# TOP.net
KiCad netlist of a schematic drawn in Altium Designer
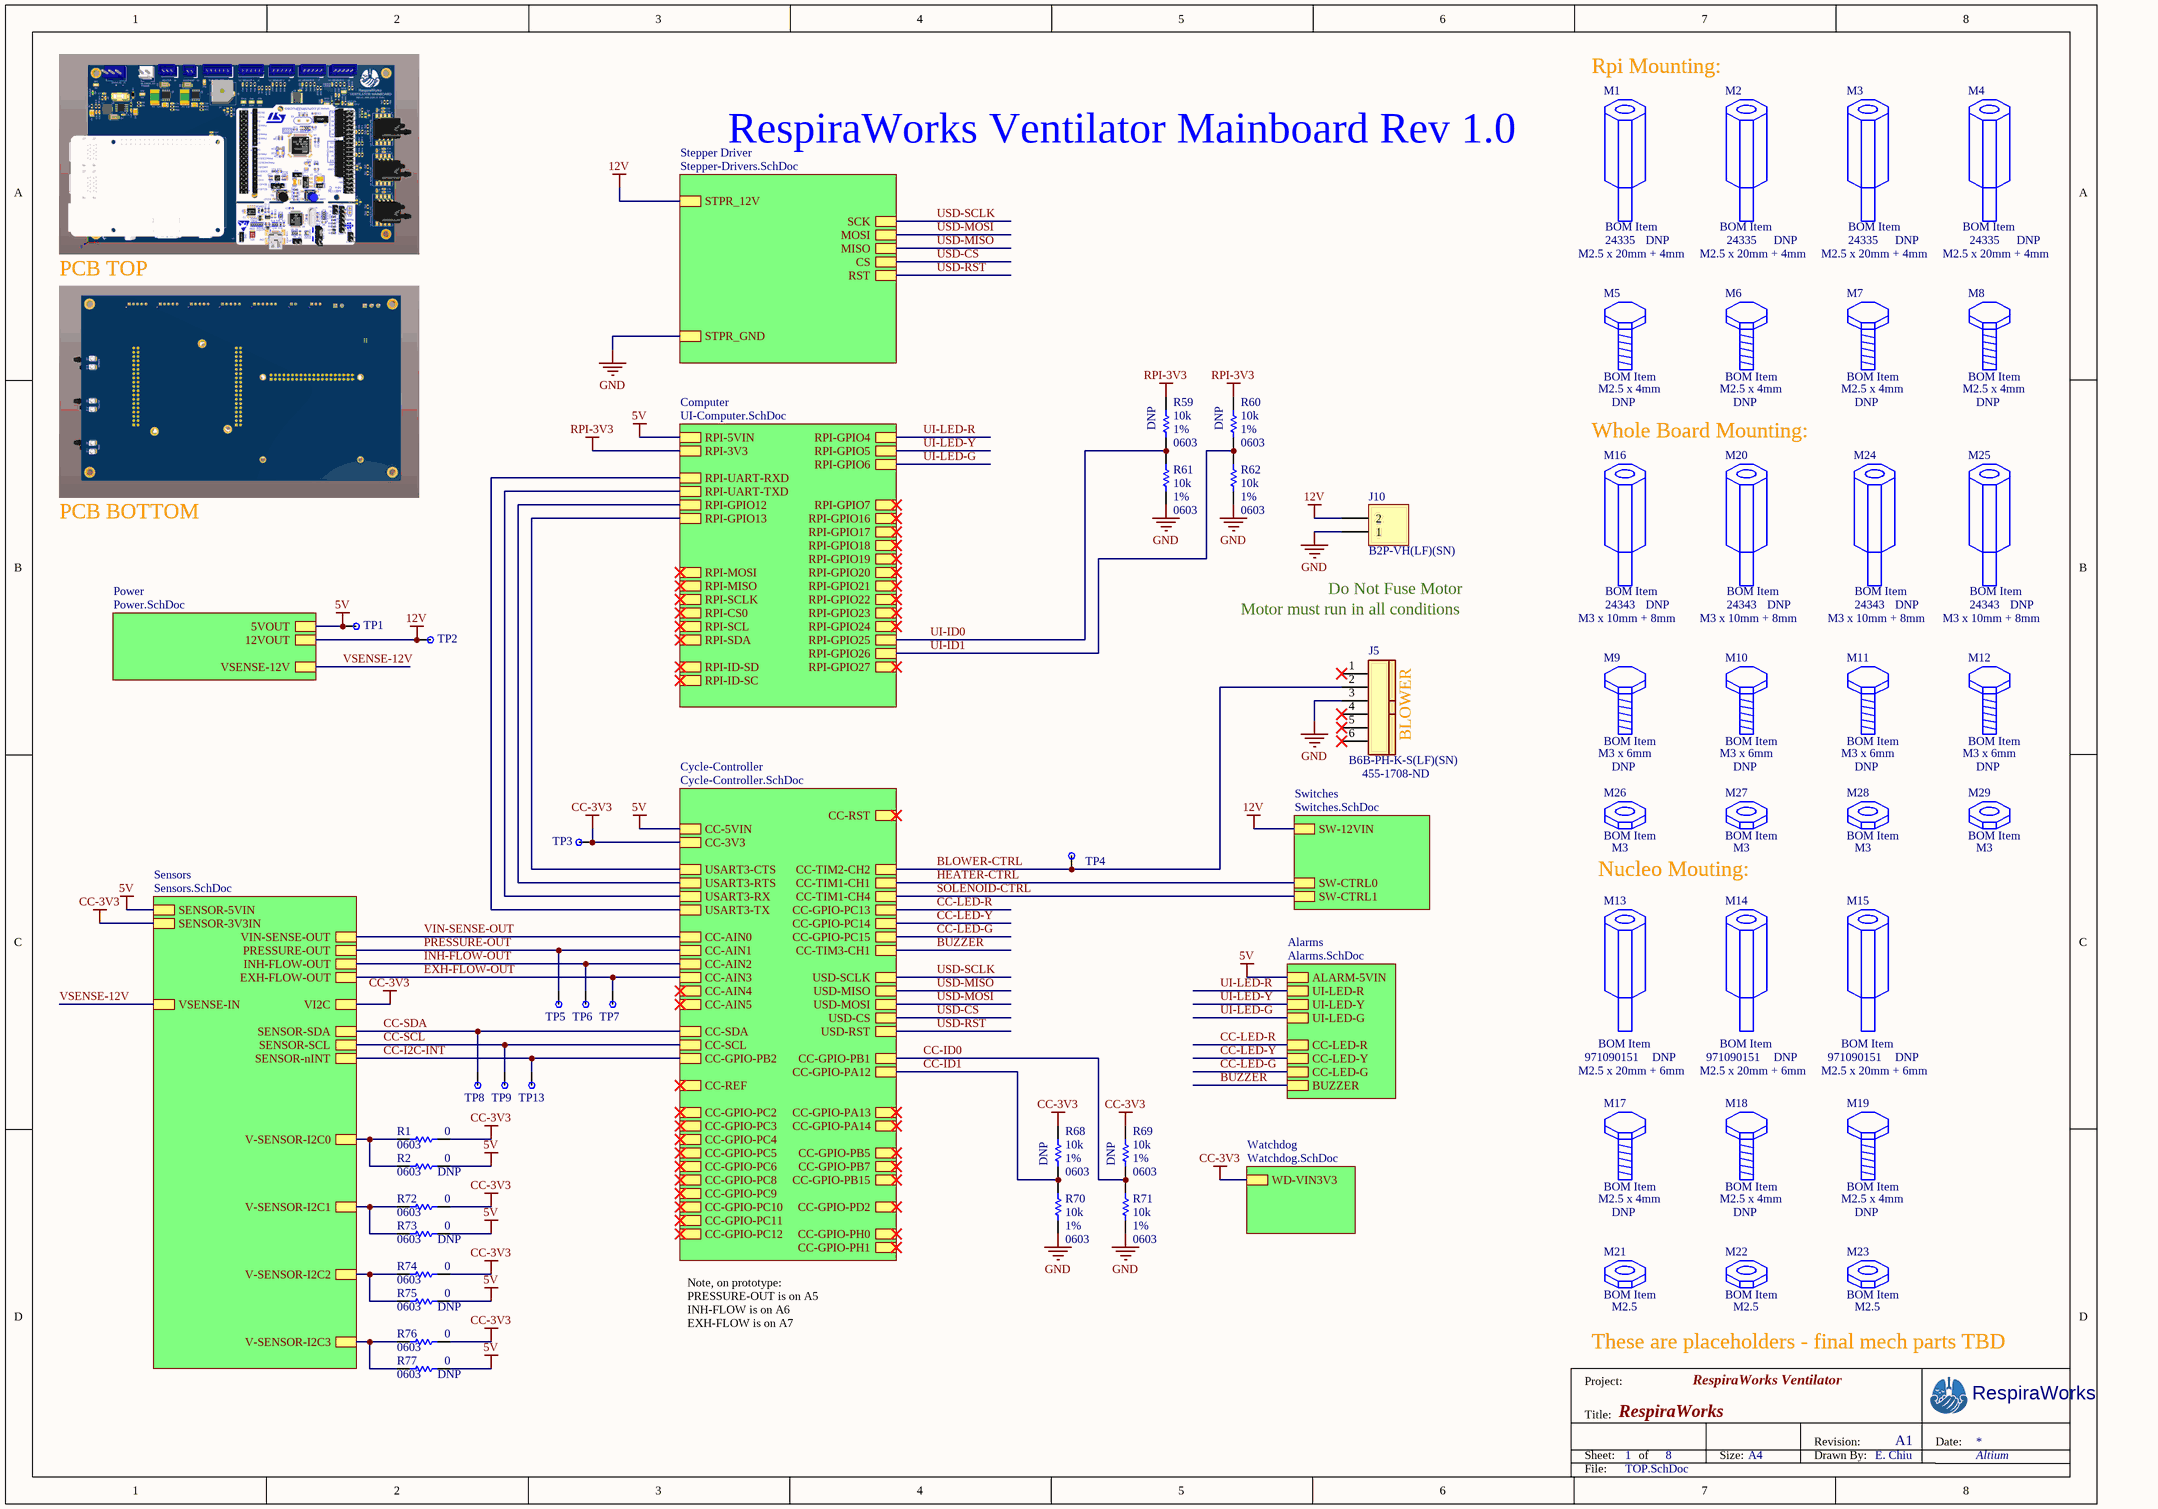
[diagram p0: TOP.SchDoc]

(export (version "E")
  (design (tool "Eeschema 10.0.6"))
  (components
    (comp (ref "J5")
      (value "B6B-PH-K-S(LF)(SN)")
      (footprint "JST_B6B-XH-AM")
      (description "CONN HEADER PH TOP 6POS 2MM")
      (fields
        (field (name "MANUFACTURER") "JST Sales America Inc.")
        (field (name "SUPPLIER PART NUMBER 1") "455-1708-ND")
      )
      (libsource (lib "JST XH") (part "B6B-PH-K-S(LF)(SN)"))
    )
    (comp (ref "J10")
      (value "B2P-VH(LF)(SN)")
      (footprint "B2P-VH(LF)(SN)")
      (description "JST-VH HEADER VERT 2POS 3.96MM")
      (fields (field (name "MANUFACTURER") "JST") (field (name "MANUFACTURER P/N") "B2P-VH(LF)(SN)"))
      (libsource (lib "JST") (part "B2P-VH(LF)(SN)"))
    )
    (comp (ref "M1")
      (value "BOM Item")
      (description "[BOM Item] Generic Standoff")
      (fields
        (field (name "MANUFACTURER") "Keystone")
        (field (name "MANUFACTURER P/N") "24335")
        (field (name "DO NOT POPULATE") "DNP")
        (field (name "ALTIUM_VALUE") "M2.5 x 20mm + 4mm")
      )
      (libsource (lib "generic") (part "STANDOFF"))
    )
    (comp (ref "M2")
      (value "BOM Item")
      (description "[BOM Item] Generic Standoff")
      (fields
        (field (name "MANUFACTURER") "Keystone")
        (field (name "MANUFACTURER P/N") "24335")
        (field (name "DO NOT POPULATE") "DNP")
        (field (name "ALTIUM_VALUE") "M2.5 x 20mm + 4mm")
      )
      (libsource (lib "generic") (part "STANDOFF"))
    )
    (comp (ref "M3")
      (value "BOM Item")
      (description "[BOM Item] Generic Standoff")
      (fields
        (field (name "MANUFACTURER") "Keystone")
        (field (name "MANUFACTURER P/N") "24335")
        (field (name "DO NOT POPULATE") "DNP")
        (field (name "ALTIUM_VALUE") "M2.5 x 20mm + 4mm")
      )
      (libsource (lib "generic") (part "STANDOFF"))
    )
    (comp (ref "M4")
      (value "BOM Item")
      (description "[BOM Item] Generic Standoff")
      (fields
        (field (name "MANUFACTURER") "Keystone")
        (field (name "MANUFACTURER P/N") "24335")
        (field (name "DO NOT POPULATE") "DNP")
        (field (name "ALTIUM_VALUE") "M2.5 x 20mm + 4mm")
      )
      (libsource (lib "generic") (part "STANDOFF"))
    )
    (comp (ref "M5")
      (value "BOM Item")
      (description "[BOM Item] Generic Nut")
      (fields
        (field (name "MANUFACTURER") "Keystone")
        (field (name "DO NOT POPULATE") "DNP")
        (field (name "ALTIUM_VALUE") "M2.5 x 4mm")
      )
      (libsource (lib "generic") (part "SCREW"))
    )
    (comp (ref "M6")
      (value "BOM Item")
      (description "[BOM Item] Generic Nut")
      (fields
        (field (name "MANUFACTURER") "Keystone")
        (field (name "DO NOT POPULATE") "DNP")
        (field (name "ALTIUM_VALUE") "M2.5 x 4mm")
      )
      (libsource (lib "generic") (part "SCREW"))
    )
    (comp (ref "M7")
      (value "BOM Item")
      (description "[BOM Item] Generic Nut")
      (fields
        (field (name "MANUFACTURER") "Keystone")
        (field (name "DO NOT POPULATE") "DNP")
        (field (name "ALTIUM_VALUE") "M2.5 x 4mm")
      )
      (libsource (lib "generic") (part "SCREW"))
    )
    (comp (ref "M8")
      (value "BOM Item")
      (description "[BOM Item] Generic Nut")
      (fields
        (field (name "MANUFACTURER") "Keystone")
        (field (name "DO NOT POPULATE") "DNP")
        (field (name "ALTIUM_VALUE") "M2.5 x 4mm")
      )
      (libsource (lib "generic") (part "SCREW"))
    )
    (comp (ref "M9")
      (value "BOM Item")
      (description "[BOM Item] Generic Nut")
      (fields
        (field (name "MANUFACTURER") "Keystone")
        (field (name "DO NOT POPULATE") "DNP")
        (field (name "ALTIUM_VALUE") "M3 x 6mm")
      )
      (libsource (lib "generic") (part "SCREW"))
    )
    (comp (ref "M10")
      (value "BOM Item")
      (description "[BOM Item] Generic Nut")
      (fields
        (field (name "MANUFACTURER") "Keystone")
        (field (name "DO NOT POPULATE") "DNP")
        (field (name "ALTIUM_VALUE") "M3 x 6mm")
      )
      (libsource (lib "generic") (part "SCREW"))
    )
    (comp (ref "M11")
      (value "BOM Item")
      (description "[BOM Item] Generic Nut")
      (fields
        (field (name "MANUFACTURER") "Keystone")
        (field (name "DO NOT POPULATE") "DNP")
        (field (name "ALTIUM_VALUE") "M3 x 6mm")
      )
      (libsource (lib "generic") (part "SCREW"))
    )
    (comp (ref "M12")
      (value "BOM Item")
      (description "[BOM Item] Generic Nut")
      (fields
        (field (name "MANUFACTURER") "Keystone")
        (field (name "DO NOT POPULATE") "DNP")
        (field (name "ALTIUM_VALUE") "M3 x 6mm")
      )
      (libsource (lib "generic") (part "SCREW"))
    )
    (comp (ref "M13")
      (value "BOM Item")
      (description "[BOM Item] Generic Standoff")
      (fields
        (field (name "MANUFACTURER") "Wurth")
        (field (name "MANUFACTURER P/N") "971090151")
        (field (name "DO NOT POPULATE") "DNP")
        (field (name "ALTIUM_VALUE") "M2.5 x 20mm + 6mm")
      )
      (libsource (lib "generic") (part "STANDOFF"))
    )
    (comp (ref "M14")
      (value "BOM Item")
      (description "[BOM Item] Generic Standoff")
      (fields
        (field (name "MANUFACTURER") "Wurth")
        (field (name "MANUFACTURER P/N") "971090151")
        (field (name "DO NOT POPULATE") "DNP")
        (field (name "ALTIUM_VALUE") "M2.5 x 20mm + 6mm")
      )
      (libsource (lib "generic") (part "STANDOFF"))
    )
    (comp (ref "M15")
      (value "BOM Item")
      (description "[BOM Item] Generic Standoff")
      (fields
        (field (name "MANUFACTURER") "Wurth")
        (field (name "MANUFACTURER P/N") "971090151")
        (field (name "DO NOT POPULATE") "DNP")
        (field (name "ALTIUM_VALUE") "M2.5 x 20mm + 6mm")
      )
      (libsource (lib "generic") (part "STANDOFF"))
    )
    (comp (ref "M16")
      (value "BOM Item")
      (description "[BOM Item] Generic Standoff")
      (fields
        (field (name "MANUFACTURER") "Keystone")
        (field (name "MANUFACTURER P/N") "24343")
        (field (name "DO NOT POPULATE") "DNP")
        (field (name "ALTIUM_VALUE") "M3 x 10mm + 8mm")
      )
      (libsource (lib "generic") (part "STANDOFF"))
    )
    (comp (ref "M17")
      (value "BOM Item")
      (description "[BOM Item] Generic Nut")
      (fields
        (field (name "MANUFACTURER") "Keystone")
        (field (name "DO NOT POPULATE") "DNP")
        (field (name "ALTIUM_VALUE") "M2.5 x 4mm")
      )
      (libsource (lib "generic") (part "SCREW"))
    )
    (comp (ref "M18")
      (value "BOM Item")
      (description "[BOM Item] Generic Nut")
      (fields
        (field (name "MANUFACTURER") "Keystone")
        (field (name "DO NOT POPULATE") "DNP")
        (field (name "ALTIUM_VALUE") "M2.5 x 4mm")
      )
      (libsource (lib "generic") (part "SCREW"))
    )
    (comp (ref "M19")
      (value "BOM Item")
      (description "[BOM Item] Generic Nut")
      (fields
        (field (name "MANUFACTURER") "Keystone")
        (field (name "DO NOT POPULATE") "DNP")
        (field (name "ALTIUM_VALUE") "M2.5 x 4mm")
      )
      (libsource (lib "generic") (part "SCREW"))
    )
    (comp (ref "M20")
      (value "BOM Item")
      (description "[BOM Item] Generic Standoff")
      (fields
        (field (name "MANUFACTURER") "Keystone")
        (field (name "MANUFACTURER P/N") "24343")
        (field (name "DO NOT POPULATE") "DNP")
        (field (name "ALTIUM_VALUE") "M3 x 10mm + 8mm")
      )
      (libsource (lib "generic") (part "STANDOFF"))
    )
    (comp (ref "M21")
      (value "BOM Item")
      (description "[BOM Item] Generic Nut")
      (fields (field (name "MANUFACTURER") "Keystone") (field (name "ALTIUM_VALUE") "M2.5"))
      (libsource (lib "generic") (part "NUT"))
    )
    (comp (ref "M22")
      (value "BOM Item")
      (description "[BOM Item] Generic Nut")
      (fields (field (name "MANUFACTURER") "Keystone") (field (name "ALTIUM_VALUE") "M2.5"))
      (libsource (lib "generic") (part "NUT"))
    )
    (comp (ref "M23")
      (value "BOM Item")
      (description "[BOM Item] Generic Nut")
      (fields (field (name "MANUFACTURER") "Keystone") (field (name "ALTIUM_VALUE") "M2.5"))
      (libsource (lib "generic") (part "NUT"))
    )
    (comp (ref "M24")
      (value "BOM Item")
      (description "[BOM Item] Generic Standoff")
      (fields
        (field (name "MANUFACTURER") "Keystone")
        (field (name "MANUFACTURER P/N") "24343")
        (field (name "DO NOT POPULATE") "DNP")
        (field (name "ALTIUM_VALUE") "M3 x 10mm + 8mm")
      )
      (libsource (lib "generic") (part "STANDOFF"))
    )
    (comp (ref "M25")
      (value "BOM Item")
      (description "[BOM Item] Generic Standoff")
      (fields
        (field (name "MANUFACTURER") "Keystone")
        (field (name "MANUFACTURER P/N") "24343")
        (field (name "DO NOT POPULATE") "DNP")
        (field (name "ALTIUM_VALUE") "M3 x 10mm + 8mm")
      )
      (libsource (lib "generic") (part "STANDOFF"))
    )
    (comp (ref "M26")
      (value "BOM Item")
      (description "[BOM Item] Generic Nut")
      (fields (field (name "MANUFACTURER") "B&F") (field (name "ALTIUM_VALUE") "M3"))
      (libsource (lib "generic") (part "NUT"))
    )
    (comp (ref "M27")
      (value "BOM Item")
      (description "[BOM Item] Generic Nut")
      (fields (field (name "MANUFACTURER") "B&F") (field (name "ALTIUM_VALUE") "M3"))
      (libsource (lib "generic") (part "NUT"))
    )
    (comp (ref "M28")
      (value "BOM Item")
      (description "[BOM Item] Generic Nut")
      (fields (field (name "MANUFACTURER") "B&F") (field (name "ALTIUM_VALUE") "M3"))
      (libsource (lib "generic") (part "NUT"))
    )
    (comp (ref "M29")
      (value "BOM Item")
      (description "[BOM Item] Generic Nut")
      (fields (field (name "MANUFACTURER") "B&F") (field (name "ALTIUM_VALUE") "M3"))
      (libsource (lib "generic") (part "NUT"))
    )
    (comp (ref "R1")
      (value "0")
      (footprint "RES0603")
      (description "Res 0603")
      (fields
        (field (name "MANUFACTURER") "Yageo")
        (field (name "PCB PACKAGE") "0603")
        (field (name "TOLERANCE") "5%")
      )
      (libsource (lib "generic") (part "RES 0603"))
    )
    (comp (ref "R2")
      (value "0")
      (footprint "RES0603")
      (description "Res 0603")
      (fields
        (field (name "MANUFACTURER") "Yageo")
        (field (name "PCB PACKAGE") "0603")
        (field (name "TOLERANCE") "5%")
        (field (name "DO NOT POPULATE") "DNP")
      )
      (libsource (lib "generic") (part "RES 0603"))
    )
    (comp (ref "R59")
      (value "10k")
      (footprint "RES0603")
      (description "Res 0603")
      (fields
        (field (name "MANUFACTURER") "Panasonic")
        (field (name "PCB PACKAGE") "0603")
        (field (name "TOLERANCE") "1%")
        (field (name "DO NOT POPULATE") "DNP")
        (field (name "Comment") "RES 0603")
      )
      (libsource (lib "generic") (part "RES 0603"))
    )
    (comp (ref "R60")
      (value "10k")
      (footprint "RES0603")
      (description "Res 0603")
      (fields
        (field (name "MANUFACTURER") "Panasonic")
        (field (name "PCB PACKAGE") "0603")
        (field (name "TOLERANCE") "1%")
        (field (name "DO NOT POPULATE") "DNP")
        (field (name "Comment") "RES 0603")
      )
      (libsource (lib "generic") (part "RES 0603"))
    )
    (comp (ref "R61")
      (value "10k")
      (footprint "RES0603")
      (description "Res 0603")
      (fields
        (field (name "MANUFACTURER") "Panasonic")
        (field (name "PCB PACKAGE") "0603")
        (field (name "TOLERANCE") "1%")
        (field (name "Comment") "RES 0603")
      )
      (libsource (lib "generic") (part "RES 0603"))
    )
    (comp (ref "R62")
      (value "10k")
      (footprint "RES0603")
      (description "Res 0603")
      (fields
        (field (name "MANUFACTURER") "Panasonic")
        (field (name "PCB PACKAGE") "0603")
        (field (name "TOLERANCE") "1%")
        (field (name "Comment") "RES 0603")
      )
      (libsource (lib "generic") (part "RES 0603"))
    )
    (comp (ref "R68")
      (value "10k")
      (footprint "RES0603")
      (description "Res 0603")
      (fields
        (field (name "MANUFACTURER") "Panasonic")
        (field (name "PCB PACKAGE") "0603")
        (field (name "TOLERANCE") "1%")
        (field (name "DO NOT POPULATE") "DNP")
        (field (name "Comment") "RES 0603")
      )
      (libsource (lib "generic") (part "RES 0603"))
    )
    (comp (ref "R69")
      (value "10k")
      (footprint "RES0603")
      (description "Res 0603")
      (fields
        (field (name "MANUFACTURER") "Panasonic")
        (field (name "PCB PACKAGE") "0603")
        (field (name "TOLERANCE") "1%")
        (field (name "DO NOT POPULATE") "DNP")
        (field (name "Comment") "RES 0603")
      )
      (libsource (lib "generic") (part "RES 0603"))
    )
    (comp (ref "R70")
      (value "10k")
      (footprint "RES0603")
      (description "Res 0603")
      (fields
        (field (name "MANUFACTURER") "Panasonic")
        (field (name "PCB PACKAGE") "0603")
        (field (name "TOLERANCE") "1%")
        (field (name "Comment") "RES 0603")
      )
      (libsource (lib "generic") (part "RES 0603"))
    )
    (comp (ref "R71")
      (value "10k")
      (footprint "RES0603")
      (description "Res 0603")
      (fields
        (field (name "MANUFACTURER") "Panasonic")
        (field (name "PCB PACKAGE") "0603")
        (field (name "TOLERANCE") "1%")
        (field (name "Comment") "RES 0603")
      )
      (libsource (lib "generic") (part "RES 0603"))
    )
    (comp (ref "R72")
      (value "0")
      (footprint "RES0603")
      (description "Res 0603")
      (fields
        (field (name "MANUFACTURER") "Yageo")
        (field (name "PCB PACKAGE") "0603")
        (field (name "TOLERANCE") "5%")
      )
      (libsource (lib "generic") (part "RES 0603"))
    )
    (comp (ref "R73")
      (value "0")
      (footprint "RES0603")
      (description "Res 0603")
      (fields
        (field (name "MANUFACTURER") "Yageo")
        (field (name "PCB PACKAGE") "0603")
        (field (name "TOLERANCE") "5%")
        (field (name "DO NOT POPULATE") "DNP")
      )
      (libsource (lib "generic") (part "RES 0603"))
    )
    (comp (ref "R74")
      (value "0")
      (footprint "RES0603")
      (description "Res 0603")
      (fields
        (field (name "MANUFACTURER") "Yageo")
        (field (name "PCB PACKAGE") "0603")
        (field (name "TOLERANCE") "5%")
      )
      (libsource (lib "generic") (part "RES 0603"))
    )
    (comp (ref "R75")
      (value "0")
      (footprint "RES0603")
      (description "Res 0603")
      (fields
        (field (name "MANUFACTURER") "Yageo")
        (field (name "PCB PACKAGE") "0603")
        (field (name "TOLERANCE") "5%")
        (field (name "DO NOT POPULATE") "DNP")
      )
      (libsource (lib "generic") (part "RES 0603"))
    )
    (comp (ref "R76")
      (value "0")
      (footprint "RES0603")
      (description "Res 0603")
      (fields
        (field (name "MANUFACTURER") "Yageo")
        (field (name "PCB PACKAGE") "0603")
        (field (name "TOLERANCE") "5%")
      )
      (libsource (lib "generic") (part "RES 0603"))
    )
    (comp (ref "R77")
      (value "0")
      (footprint "RES0603")
      (description "Res 0603")
      (fields
        (field (name "MANUFACTURER") "Yageo")
        (field (name "PCB PACKAGE") "0603")
        (field (name "TOLERANCE") "5%")
        (field (name "DO NOT POPULATE") "DNP")
      )
      (libsource (lib "generic") (part "RES 0603"))
    )
    (comp (ref "TP1")
      (value "TP-SMT")
      (footprint "TP-5015")
      (description "Keystone 5015 SMT Mini Testpoint")
      (fields (field (name "MANUFACTURER") "Keystone") (field (name "TOLERANCE") "5015"))
      (libsource (lib "generic") (part "TP-SMT"))
    )
    (comp (ref "TP2")
      (value "TP-SMT")
      (footprint "TP-5015")
      (description "Keystone 5015 SMT Mini Testpoint")
      (fields (field (name "MANUFACTURER") "Keystone") (field (name "TOLERANCE") "5015"))
      (libsource (lib "generic") (part "TP-SMT"))
    )
    (comp (ref "TP3")
      (value "TP-SMT")
      (footprint "TP-5015")
      (description "Keystone 5015 SMT Mini Testpoint")
      (fields (field (name "MANUFACTURER") "Keystone") (field (name "TOLERANCE") "5015"))
      (libsource (lib "generic") (part "TP-SMT"))
    )
    (comp (ref "TP4")
      (value "TP-SMT")
      (footprint "TP-5015")
      (description "Keystone 5015 SMT Mini Testpoint")
      (fields (field (name "MANUFACTURER") "Keystone") (field (name "TOLERANCE") "5015"))
      (libsource (lib "generic") (part "TP-SMT"))
    )
    (comp (ref "TP5")
      (value "TP-SMT")
      (footprint "TP-5015")
      (description "Keystone 5015 SMT Mini Testpoint")
      (fields (field (name "MANUFACTURER") "Keystone") (field (name "TOLERANCE") "5015"))
      (libsource (lib "generic") (part "TP-SMT"))
    )
    (comp (ref "TP6")
      (value "TP-SMT")
      (footprint "TP-5015")
      (description "Keystone 5015 SMT Mini Testpoint")
      (fields (field (name "MANUFACTURER") "Keystone") (field (name "TOLERANCE") "5015"))
      (libsource (lib "generic") (part "TP-SMT"))
    )
    (comp (ref "TP7")
      (value "TP-SMT")
      (footprint "TP-5015")
      (description "Keystone 5015 SMT Mini Testpoint")
      (fields (field (name "MANUFACTURER") "Keystone") (field (name "TOLERANCE") "5015"))
      (libsource (lib "generic") (part "TP-SMT"))
    )
    (comp (ref "TP8")
      (value "TP-SMT")
      (footprint "TP-5015")
      (description "Keystone 5015 SMT Mini Testpoint")
      (fields (field (name "MANUFACTURER") "Keystone") (field (name "TOLERANCE") "5015"))
      (libsource (lib "generic") (part "TP-SMT"))
    )
    (comp (ref "TP9")
      (value "TP-SMT")
      (footprint "TP-5015")
      (description "Keystone 5015 SMT Mini Testpoint")
      (fields (field (name "MANUFACTURER") "Keystone") (field (name "TOLERANCE") "5015"))
      (libsource (lib "generic") (part "TP-SMT"))
    )
    (comp (ref "TP13")
      (value "TP-SMT")
      (footprint "TP-5015")
      (description "Keystone 5015 SMT Mini Testpoint")
      (fields (field (name "MANUFACTURER") "Keystone") (field (name "TOLERANCE") "5015"))
      (libsource (lib "generic") (part "TP-SMT"))
    )
  )
  (nets
    (net (code "1") (name "/BLOWER-CTRL") (class "Default")
      (node (ref "J5") (pin "2") (pinfunction "2_2") (pintype "passive"))
      (node (ref "TP4") (pin "1") (pinfunction "1_1") (pintype "passive"))
    )
    (net (code "23") (name "/CC-I2C-INT") (class "Default")
      (node (ref "TP13") (pin "1") (pinfunction "1_1") (pintype "passive"))
    )
    (net (code "24") (name "/CC-ID0") (class "Default")
      (node (ref "R69") (pin "1") (pinfunction "1_1") (pintype "passive"))
      (node (ref "R71") (pin "2") (pinfunction "2_2") (pintype "passive"))
    )
    (net (code "25") (name "/CC-ID1") (class "Default")
      (node (ref "R68") (pin "1") (pinfunction "1_1") (pintype "passive"))
      (node (ref "R70") (pin "2") (pinfunction "2_2") (pintype "passive"))
    )
    (net (code "31") (name "/CC-SCL") (class "Default")
      (node (ref "TP9") (pin "1") (pinfunction "1_1") (pintype "passive"))
    )
    (net (code "32") (name "/CC-SDA") (class "Default")
      (node (ref "TP8") (pin "1") (pinfunction "1_1") (pintype "passive"))
    )
    (net (code "33") (name "/EXH-FLOW-OUT") (class "Default")
      (node (ref "TP7") (pin "1") (pinfunction "1_1") (pintype "passive"))
    )
    (net (code "35") (name "/INH-FLOW-OUT") (class "Default")
      (node (ref "TP6") (pin "1") (pinfunction "1_1") (pintype "passive"))
    )
    (net (code "36") (name "/PRESSURE-OUT") (class "Default")
      (node (ref "TP5") (pin "1") (pinfunction "1_1") (pintype "passive"))
    )
    (net (code "61") (name "/UI-ID0") (class "Default")
      (node (ref "R59") (pin "1") (pinfunction "1_1") (pintype "passive"))
      (node (ref "R61") (pin "2") (pinfunction "2_2") (pintype "passive"))
    )
    (net (code "62") (name "/UI-ID1") (class "Default")
      (node (ref "R60") (pin "1") (pinfunction "1_1") (pintype "passive"))
      (node (ref "R62") (pin "2") (pinfunction "2_2") (pintype "passive"))
    )
    (net (code "71") (name "/V-SENSOR-I2C0") (class "Default")
      (node (ref "R1") (pin "1") (pinfunction "1_1") (pintype "passive"))
      (node (ref "R2") (pin "1") (pinfunction "1_1") (pintype "passive"))
    )
    (net (code "72") (name "/V-SENSOR-I2C1") (class "Default")
      (node (ref "R72") (pin "1") (pinfunction "1_1") (pintype "passive"))
      (node (ref "R73") (pin "1") (pinfunction "1_1") (pintype "passive"))
    )
    (net (code "73") (name "/V-SENSOR-I2C2") (class "Default")
      (node (ref "R74") (pin "1") (pinfunction "1_1") (pintype "passive"))
      (node (ref "R75") (pin "1") (pinfunction "1_1") (pintype "passive"))
    )
    (net (code "74") (name "/V-SENSOR-I2C3") (class "Default")
      (node (ref "R76") (pin "1") (pinfunction "1_1") (pintype "passive"))
      (node (ref "R77") (pin "1") (pinfunction "1_1") (pintype "passive"))
    )
    (net (code "77") (name "5V") (class "Default")
      (node (ref "R2") (pin "2") (pinfunction "2_2") (pintype "passive"))
      (node (ref "R73") (pin "2") (pinfunction "2_2") (pintype "passive"))
      (node (ref "R75") (pin "2") (pinfunction "2_2") (pintype "passive"))
      (node (ref "R77") (pin "2") (pinfunction "2_2") (pintype "passive"))
      (node (ref "TP1") (pin "1") (pinfunction "1_1") (pintype "passive"))
    )
    (net (code "78") (name "12V") (class "Default")
      (node (ref "J10") (pin "2") (pinfunction "2_2") (pintype "passive"))
      (node (ref "TP2") (pin "1") (pinfunction "1_1") (pintype "passive"))
    )
    (net (code "79") (name "CC-3V3") (class "Default")
      (node (ref "R1") (pin "2") (pinfunction "2_2") (pintype "passive"))
      (node (ref "R68") (pin "2") (pinfunction "2_2") (pintype "passive"))
      (node (ref "R69") (pin "2") (pinfunction "2_2") (pintype "passive"))
      (node (ref "R72") (pin "2") (pinfunction "2_2") (pintype "passive"))
      (node (ref "R74") (pin "2") (pinfunction "2_2") (pintype "passive"))
      (node (ref "R76") (pin "2") (pinfunction "2_2") (pintype "passive"))
      (node (ref "TP3") (pin "1") (pinfunction "1_1") (pintype "passive"))
    )
    (net (code "80") (name "GND") (class "Default")
      (node (ref "J10") (pin "1") (pinfunction "1_1") (pintype "passive"))
      (node (ref "J5") (pin "3") (pinfunction "3_3") (pintype "passive"))
      (node (ref "R61") (pin "1") (pinfunction "1_1") (pintype "passive"))
      (node (ref "R62") (pin "1") (pinfunction "1_1") (pintype "passive"))
      (node (ref "R70") (pin "1") (pinfunction "1_1") (pintype "passive"))
      (node (ref "R71") (pin "1") (pinfunction "1_1") (pintype "passive"))
    )
    (net (code "81") (name "RPI-3V3") (class "Default")
      (node (ref "R59") (pin "2") (pinfunction "2_2") (pintype "passive"))
      (node (ref "R60") (pin "2") (pinfunction "2_2") (pintype "passive"))
    )
    (net (code "82") (name "unconnected-(J5-Pad1)") (class "Default")
      (node (ref "J5") (pin "1") (pinfunction "1_1") (pintype "passive+no_connect"))
    )
    (net (code "83") (name "unconnected-(J5-Pad4)") (class "Default")
      (node (ref "J5") (pin "4") (pinfunction "4_4") (pintype "passive+no_connect"))
    )
    (net (code "84") (name "unconnected-(J5-Pad5)") (class "Default")
      (node (ref "J5") (pin "5") (pinfunction "5_5") (pintype "passive+no_connect"))
    )
    (net (code "85") (name "unconnected-(J5-Pad6)") (class "Default")
      (node (ref "J5") (pin "6") (pinfunction "6_6") (pintype "passive+no_connect"))
    )
  )
)
